# base_board5.net
KiCad netlist of a schematic drawn in EAGLE
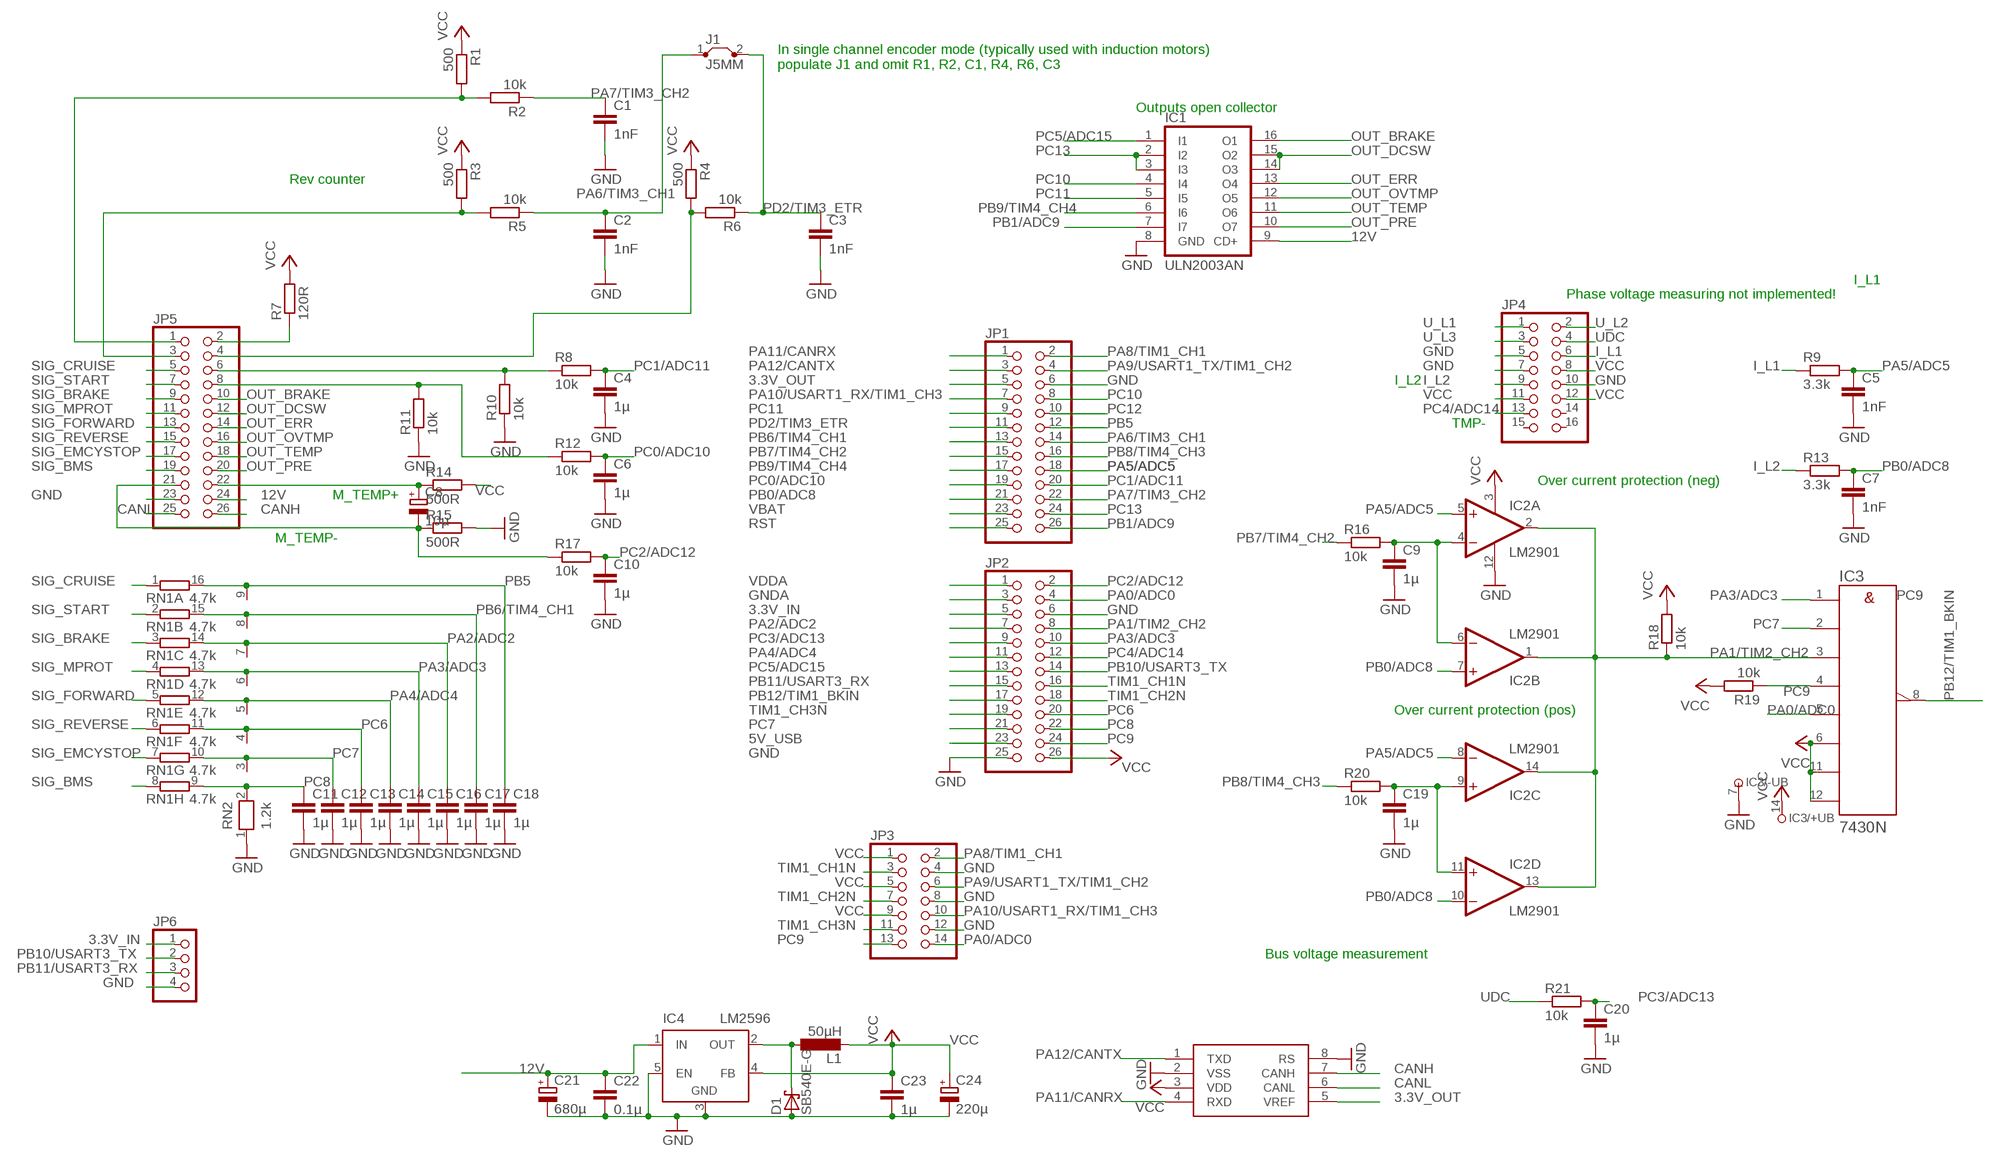
[diagram p0: schematic, sheet 1]

(export (version "E")
  (design (tool "Eeschema 10.0.6"))
  (components
    (comp (ref "C1")
      (value "1nF")
      (footprint "eagle-import:C025-024X044")
      (libsource (lib "eagle-import") (part "C-EU025-024X044"))
    )
    (comp (ref "C2")
      (value "1nF")
      (footprint "eagle-import:C025-024X044")
      (libsource (lib "eagle-import") (part "C-EU025-024X044"))
    )
    (comp (ref "C3")
      (value "1nF")
      (footprint "eagle-import:C025-024X044")
      (libsource (lib "eagle-import") (part "C-EU025-024X044"))
    )
    (comp (ref "C4")
      (value "1µ")
      (footprint "eagle-import:C025-024X044")
      (libsource (lib "eagle-import") (part "C-EU025-024X044"))
    )
    (comp (ref "C5")
      (value "1nF")
      (footprint "eagle-import:C025-024X044")
      (libsource (lib "eagle-import") (part "C-EU025-024X044"))
    )
    (comp (ref "C6")
      (value "1µ")
      (footprint "eagle-import:C025-024X044")
      (libsource (lib "eagle-import") (part "C-EU025-024X044"))
    )
    (comp (ref "C7")
      (value "1nF")
      (footprint "eagle-import:C025-024X044")
      (libsource (lib "eagle-import") (part "C-EU025-024X044"))
    )
    (comp (ref "C8")
      (value "10µ")
      (footprint "eagle-import:E2-4")
      (libsource (lib "eagle-import") (part "CPOL-EUE2-4"))
    )
    (comp (ref "C9")
      (value "1µ")
      (footprint "eagle-import:C025-024X044")
      (libsource (lib "eagle-import") (part "C-EU025-024X044"))
    )
    (comp (ref "C10")
      (value "1µ")
      (footprint "eagle-import:C025-024X044")
      (libsource (lib "eagle-import") (part "C-EU025-024X044"))
    )
    (comp (ref "C11")
      (value "1µ")
      (footprint "eagle-import:C025-024X044")
      (libsource (lib "eagle-import") (part "C-EU025-024X044"))
    )
    (comp (ref "C12")
      (value "1µ")
      (footprint "eagle-import:C025-024X044")
      (libsource (lib "eagle-import") (part "C-EU025-024X044"))
    )
    (comp (ref "C13")
      (value "1µ")
      (footprint "eagle-import:C025-024X044")
      (libsource (lib "eagle-import") (part "C-EU025-024X044"))
    )
    (comp (ref "C14")
      (value "1µ")
      (footprint "eagle-import:C025-024X044")
      (libsource (lib "eagle-import") (part "C-EU025-024X044"))
    )
    (comp (ref "C15")
      (value "1µ")
      (footprint "eagle-import:C025-024X044")
      (libsource (lib "eagle-import") (part "C-EU025-024X044"))
    )
    (comp (ref "C16")
      (value "1µ")
      (footprint "eagle-import:C025-024X044")
      (libsource (lib "eagle-import") (part "C-EU025-024X044"))
    )
    (comp (ref "C17")
      (value "1µ")
      (footprint "eagle-import:C025-024X044")
      (libsource (lib "eagle-import") (part "C-EU025-024X044"))
    )
    (comp (ref "C18")
      (value "1µ")
      (footprint "eagle-import:C025-024X044")
      (libsource (lib "eagle-import") (part "C-EU025-024X044"))
    )
    (comp (ref "C19")
      (value "1µ")
      (footprint "eagle-import:C025-024X044")
      (libsource (lib "eagle-import") (part "C-EU025-024X044"))
    )
    (comp (ref "C20")
      (value "1µ")
      (footprint "eagle-import:C025-024X044")
      (libsource (lib "eagle-import") (part "C-EU025-024X044"))
    )
    (comp (ref "C21")
      (value "680µ")
      (footprint "eagle-import:E2,5-5")
      (libsource (lib "eagle-import") (part "CPOL-EUE2.5-5"))
    )
    (comp (ref "C22")
      (value "0.1µ")
      (footprint "eagle-import:C050-024X044")
      (libsource (lib "eagle-import") (part "C-EU050-024X044"))
    )
    (comp (ref "C23")
      (value "1µ")
      (footprint "eagle-import:C025-024X044")
      (libsource (lib "eagle-import") (part "C-EU025-024X044"))
    )
    (comp (ref "C24")
      (value "220µ")
      (footprint "eagle-import:E2-4")
      (libsource (lib "eagle-import") (part "CPOL-EUE2-4"))
    )
    (comp (ref "D1")
      (value "SB540E-G")
      (footprint "eagle-import:DO201T15")
      (libsource (lib "eagle-import") (part "SCHOTTKY-DIODEDO201T15"))
    )
    (comp (ref "IC1")
      (value "ULN2003AN")
      (footprint "eagle-import:DIL16")
      (libsource (lib "eagle-import") (part "ULN2001AN"))
    )
    (comp (ref "IC2")
      (value "LM2901")
      (footprint "eagle-import:DIL14")
      (libsource (lib "eagle-import") (part "LM339N"))
    )
    (comp (ref "IC3")
      (value "7430N")
      (footprint "eagle-import:DIL14")
      (libsource (lib "eagle-import") (part "7430N"))
    )
    (comp (ref "IC4")
      (value "LM2596")
      (footprint "eagle-import:TO220-51")
      (libsource (lib "eagle-import") (part "LM2596TV"))
    )
    (comp (ref "IC5")
      (value "MCP2562P")
      (footprint "eagle-import:DIL08")
      (libsource (lib "eagle-import") (part "MCP2551P"))
    )
    (comp (ref "J1")
      (value "J5MM")
      (footprint "eagle-import:05")
      (libsource (lib "eagle-import") (part "J5MM"))
    )
    (comp (ref "JP1")
      (value "PINHD-2X13")
      (footprint "eagle-import:2X13")
      (libsource (lib "eagle-import") (part "PINHD-2X13"))
    )
    (comp (ref "JP2")
      (value "PINHD-2X13")
      (footprint "eagle-import:2X13")
      (libsource (lib "eagle-import") (part "PINHD-2X13"))
    )
    (comp (ref "JP3")
      (value "PINHD-2X7")
      (footprint "eagle-import:2X07")
      (libsource (lib "eagle-import") (part "PINHD-2X7"))
    )
    (comp (ref "JP4")
      (value "PINHD-2X8")
      (footprint "eagle-import:2X08")
      (libsource (lib "eagle-import") (part "PINHD-2X8"))
    )
    (comp (ref "JP5")
      (value "PINHD-2X13")
      (footprint "eagle-import:2X13")
      (libsource (lib "eagle-import") (part "PINHD-2X13"))
    )
    (comp (ref "JP6")
      (value "PINHD-1X4")
      (footprint "eagle-import:1X04")
      (libsource (lib "eagle-import") (part "PINHD-1X4"))
    )
    (comp (ref "L1")
      (value "50µH")
      (footprint "eagle-import:TJ3-U1")
      (libsource (lib "eagle-import") (part "L-EUTJ3-U1"))
    )
    (comp (ref "R1")
      (value "500")
      (footprint "eagle-import:0207_10")
      (libsource (lib "eagle-import") (part "R-EU_0207/10"))
    )
    (comp (ref "R2")
      (value "10k")
      (footprint "eagle-import:0207_10")
      (libsource (lib "eagle-import") (part "R-EU_0207/10"))
    )
    (comp (ref "R3")
      (value "500")
      (footprint "eagle-import:0207_10")
      (libsource (lib "eagle-import") (part "R-EU_0207/10"))
    )
    (comp (ref "R4")
      (value "500")
      (footprint "eagle-import:0207_10")
      (libsource (lib "eagle-import") (part "R-EU_0207/10"))
    )
    (comp (ref "R5")
      (value "10k")
      (footprint "eagle-import:0207_10")
      (libsource (lib "eagle-import") (part "R-EU_0207/10"))
    )
    (comp (ref "R6")
      (value "10k")
      (footprint "eagle-import:0207_10")
      (libsource (lib "eagle-import") (part "R-EU_0207/10"))
    )
    (comp (ref "R7")
      (value "120R")
      (footprint "eagle-import:0207_10")
      (libsource (lib "eagle-import") (part "R-EU_0207/10"))
    )
    (comp (ref "R8")
      (value "10k")
      (footprint "eagle-import:0207_10")
      (libsource (lib "eagle-import") (part "R-EU_0207/10"))
    )
    (comp (ref "R9")
      (value "3.3k")
      (footprint "eagle-import:0207_10")
      (libsource (lib "eagle-import") (part "R-EU_0207/10"))
    )
    (comp (ref "R10")
      (value "10k")
      (footprint "eagle-import:0207_10")
      (libsource (lib "eagle-import") (part "R-EU_0207/10"))
    )
    (comp (ref "R11")
      (value "10k")
      (footprint "eagle-import:0207_10")
      (libsource (lib "eagle-import") (part "R-EU_0207/10"))
    )
    (comp (ref "R12")
      (value "10k")
      (footprint "eagle-import:0207_10")
      (libsource (lib "eagle-import") (part "R-EU_0207/10"))
    )
    (comp (ref "R13")
      (value "3.3k")
      (footprint "eagle-import:0207_10")
      (libsource (lib "eagle-import") (part "R-EU_0207/10"))
    )
    (comp (ref "R14")
      (value "500R")
      (footprint "eagle-import:0207_10")
      (libsource (lib "eagle-import") (part "R-EU_0207/10"))
    )
    (comp (ref "R15")
      (value "500R")
      (footprint "eagle-import:0207_10")
      (libsource (lib "eagle-import") (part "R-EU_0207/10"))
    )
    (comp (ref "R16")
      (value "10k")
      (footprint "eagle-import:0207_10")
      (libsource (lib "eagle-import") (part "R-EU_0207/10"))
    )
    (comp (ref "R17")
      (value "10k")
      (footprint "eagle-import:0207_10")
      (libsource (lib "eagle-import") (part "R-EU_0207/10"))
    )
    (comp (ref "R18")
      (value "10k")
      (footprint "eagle-import:0207_10")
      (libsource (lib "eagle-import") (part "R-EU_0207/10"))
    )
    (comp (ref "R19")
      (value "10k")
      (footprint "eagle-import:0207_10")
      (libsource (lib "eagle-import") (part "R-EU_0207/10"))
    )
    (comp (ref "R20")
      (value "10k")
      (footprint "eagle-import:0207_10")
      (libsource (lib "eagle-import") (part "R-EU_0207/10"))
    )
    (comp (ref "R21")
      (value "10k")
      (footprint "eagle-import:0207_10")
      (libsource (lib "eagle-import") (part "R-EU_0207/10"))
    )
    (comp (ref "RN1")
      (value "4.7k")
      (footprint "eagle-import:DIL16")
      (libsource (lib "eagle-import") (part "8R-N"))
    )
    (comp (ref "RN2")
      (value "1.2k")
      (footprint "eagle-import:RN-9")
      (libsource (lib "eagle-import") (part "RN08"))
    )
  )
  (nets
    (net (code "1") (name "/3.3V_IN") (class "Default")
      (node (ref "JP2") (pin "5") (pinfunction "5_5") (pintype "passive"))
      (node (ref "JP6") (pin "1") (pinfunction "1_1") (pintype "passive"))
    )
    (net (code "2") (name "/3.3V_OUT") (class "Default")
      (node (ref "IC5") (pin "5") (pinfunction "VREF_5") (pintype "bidirectional"))
      (node (ref "JP1") (pin "5") (pinfunction "5_5") (pintype "passive"))
    )
    (net (code "3") (name "/5V_USB") (class "Default")
      (node (ref "JP2") (pin "23") (pinfunction "23_23") (pintype "passive"))
    )
    (net (code "4") (name "/12V") (class "Default")
      (node (ref "C21") (pin "+") (pinfunction "+_+") (pintype "passive"))
      (node (ref "C22") (pin "1") (pinfunction "1_1") (pintype "passive"))
      (node (ref "IC1") (pin "9") (pinfunction "CD+_9") (pintype "passive"))
      (node (ref "IC4") (pin "1") (pinfunction "IN_1") (pintype "input"))
      (node (ref "JP5") (pin "24") (pinfunction "24_24") (pintype "passive"))
    )
    (net (code "5") (name "/CANH") (class "Default")
      (node (ref "IC5") (pin "7") (pinfunction "CANH_7") (pintype "bidirectional"))
      (node (ref "JP5") (pin "26") (pinfunction "26_26") (pintype "passive"))
    )
    (net (code "6") (name "/CANL") (class "Default")
      (node (ref "IC5") (pin "6") (pinfunction "CANL_6") (pintype "bidirectional"))
      (node (ref "JP5") (pin "25") (pinfunction "25_25") (pintype "passive"))
    )
    (net (code "7") (name "/GNDA") (class "Default")
      (node (ref "JP2") (pin "3") (pinfunction "3_3") (pintype "passive"))
    )
    (net (code "8") (name "/I_L1") (class "Default")
      (node (ref "JP4") (pin "6") (pinfunction "6_6") (pintype "passive"))
      (node (ref "R9") (pin "1") (pinfunction "1_1") (pintype "passive"))
    )
    (net (code "9") (name "/I_L2") (class "Default")
      (node (ref "JP4") (pin "9") (pinfunction "9_9") (pintype "passive"))
      (node (ref "R13") (pin "1") (pinfunction "1_1") (pintype "passive"))
    )
    (net (code "10") (name "/OUT_BRAKE") (class "Default")
      (node (ref "IC1") (pin "16") (pinfunction "O1_16") (pintype "open_collector"))
      (node (ref "JP5") (pin "10") (pinfunction "10_10") (pintype "passive"))
    )
    (net (code "11") (name "/OUT_DCSW") (class "Default")
      (node (ref "IC1") (pin "14") (pinfunction "O3_14") (pintype "open_collector"))
      (node (ref "IC1") (pin "15") (pinfunction "O2_15") (pintype "open_collector"))
      (node (ref "JP5") (pin "12") (pinfunction "12_12") (pintype "passive"))
    )
    (net (code "12") (name "/OUT_ERR") (class "Default")
      (node (ref "IC1") (pin "13") (pinfunction "O4_13") (pintype "open_collector"))
      (node (ref "JP5") (pin "14") (pinfunction "14_14") (pintype "passive"))
    )
    (net (code "13") (name "/OUT_OVTMP") (class "Default")
      (node (ref "IC1") (pin "12") (pinfunction "O5_12") (pintype "open_collector"))
      (node (ref "JP5") (pin "16") (pinfunction "16_16") (pintype "passive"))
    )
    (net (code "14") (name "/OUT_PRE") (class "Default")
      (node (ref "IC1") (pin "10") (pinfunction "O7_10") (pintype "open_collector"))
      (node (ref "JP5") (pin "20") (pinfunction "20_20") (pintype "passive"))
    )
    (net (code "15") (name "/OUT_TEMP") (class "Default")
      (node (ref "IC1") (pin "11") (pinfunction "O6_11") (pintype "open_collector"))
      (node (ref "JP5") (pin "18") (pinfunction "18_18") (pintype "passive"))
    )
    (net (code "16") (name "/PA0{slash}ADC0") (class "Default")
      (node (ref "IC3") (pin "5") (pinfunction "E_5") (pintype "input"))
      (node (ref "JP2") (pin "4") (pinfunction "4_4") (pintype "passive"))
      (node (ref "JP3") (pin "14") (pinfunction "14_14") (pintype "passive"))
    )
    (net (code "17") (name "/PA1{slash}TIM2_CH2") (class "Default")
      (node (ref "IC2") (pin "1") (pinfunction "OUT_1") (pintype "open_collector"))
      (node (ref "IC2") (pin "13") (pinfunction "OUT_13") (pintype "open_collector"))
      (node (ref "IC2") (pin "14") (pinfunction "OUT_14") (pintype "open_collector"))
      (node (ref "IC2") (pin "2") (pinfunction "OUT_2") (pintype "open_collector"))
      (node (ref "IC3") (pin "3") (pinfunction "C_3") (pintype "input"))
      (node (ref "JP2") (pin "8") (pinfunction "8_8") (pintype "passive"))
      (node (ref "R18") (pin "1") (pinfunction "1_1") (pintype "passive"))
    )
    (net (code "18") (name "/PA2{slash}ADC2") (class "Default")
      (node (ref "C16") (pin "1") (pinfunction "1_1") (pintype "passive"))
      (node (ref "JP2") (pin "7") (pinfunction "7_7") (pintype "passive"))
      (node (ref "RN1") (pin "14") (pinfunction "2_14") (pintype "passive"))
      (node (ref "RN2") (pin "7") (pinfunction "7_7") (pintype "passive"))
    )
    (net (code "19") (name "/PA3{slash}ADC3") (class "Default")
      (node (ref "C15") (pin "1") (pinfunction "1_1") (pintype "passive"))
      (node (ref "IC3") (pin "1") (pinfunction "A_1") (pintype "input"))
      (node (ref "JP2") (pin "10") (pinfunction "10_10") (pintype "passive"))
      (node (ref "RN1") (pin "13") (pinfunction "2_13") (pintype "passive"))
      (node (ref "RN2") (pin "6") (pinfunction "6_6") (pintype "passive"))
    )
    (net (code "20") (name "/PA4{slash}ADC4") (class "Default")
      (node (ref "C14") (pin "1") (pinfunction "1_1") (pintype "passive"))
      (node (ref "JP2") (pin "11") (pinfunction "11_11") (pintype "passive"))
      (node (ref "RN1") (pin "12") (pinfunction "2_12") (pintype "passive"))
      (node (ref "RN2") (pin "5") (pinfunction "5_5") (pintype "passive"))
    )
    (net (code "21") (name "/PA5{slash}ADC5") (class "Default")
      (node (ref "C5") (pin "1") (pinfunction "1_1") (pintype "passive"))
      (node (ref "IC2") (pin "5") (pinfunction "+IN_5") (pintype "input"))
      (node (ref "IC2") (pin "8") (pinfunction "-IN_8") (pintype "input"))
      (node (ref "JP1") (pin "18") (pinfunction "18_18") (pintype "passive"))
      (node (ref "R9") (pin "2") (pinfunction "2_2") (pintype "passive"))
    )
    (net (code "22") (name "/PA6{slash}TIM3_CH1") (class "Default")
      (node (ref "C2") (pin "1") (pinfunction "1_1") (pintype "passive"))
      (node (ref "J1") (pin "1") (pinfunction "1_1") (pintype "passive"))
      (node (ref "JP1") (pin "14") (pinfunction "14_14") (pintype "passive"))
      (node (ref "R5") (pin "1") (pinfunction "1_1") (pintype "passive"))
    )
    (net (code "23") (name "/PA7{slash}TIM3_CH2") (class "Default")
      (node (ref "C1") (pin "1") (pinfunction "1_1") (pintype "passive"))
      (node (ref "JP1") (pin "22") (pinfunction "22_22") (pintype "passive"))
      (node (ref "R2") (pin "1") (pinfunction "1_1") (pintype "passive"))
    )
    (net (code "24") (name "/PA8{slash}TIM1_CH1") (class "Default")
      (node (ref "JP1") (pin "2") (pinfunction "2_2") (pintype "passive"))
      (node (ref "JP3") (pin "2") (pinfunction "2_2") (pintype "passive"))
    )
    (net (code "25") (name "/PA9{slash}USART1_TX{slash}TIM1_CH2") (class "Default")
      (node (ref "JP1") (pin "4") (pinfunction "4_4") (pintype "passive"))
      (node (ref "JP3") (pin "6") (pinfunction "6_6") (pintype "passive"))
    )
    (net (code "26") (name "/PA10{slash}USART1_RX{slash}TIM1_CH3") (class "Default")
      (node (ref "JP1") (pin "7") (pinfunction "7_7") (pintype "passive"))
      (node (ref "JP3") (pin "10") (pinfunction "10_10") (pintype "passive"))
    )
    (net (code "27") (name "/PA11{slash}CANRX") (class "Default")
      (node (ref "IC5") (pin "4") (pinfunction "RXD_4") (pintype "bidirectional"))
      (node (ref "JP1") (pin "1") (pinfunction "1_1") (pintype "passive"))
    )
    (net (code "28") (name "/PA12{slash}CANTX") (class "Default")
      (node (ref "IC5") (pin "1") (pinfunction "TXD_1") (pintype "bidirectional"))
      (node (ref "JP1") (pin "3") (pinfunction "3_3") (pintype "passive"))
    )
    (net (code "29") (name "/PB0{slash}ADC8") (class "Default")
      (node (ref "C7") (pin "1") (pinfunction "1_1") (pintype "passive"))
      (node (ref "IC2") (pin "10") (pinfunction "-IN_10") (pintype "input"))
      (node (ref "IC2") (pin "7") (pinfunction "+IN_7") (pintype "input"))
      (node (ref "JP1") (pin "21") (pinfunction "21_21") (pintype "passive"))
      (node (ref "R13") (pin "2") (pinfunction "2_2") (pintype "passive"))
    )
    (net (code "30") (name "/PB1{slash}ADC9") (class "Default")
      (node (ref "IC1") (pin "7") (pinfunction "I7_7") (pintype "input"))
      (node (ref "JP1") (pin "26") (pinfunction "26_26") (pintype "passive"))
    )
    (net (code "31") (name "/PB5") (class "Default")
      (node (ref "C18") (pin "1") (pinfunction "1_1") (pintype "passive"))
      (node (ref "JP1") (pin "12") (pinfunction "12_12") (pintype "passive"))
      (node (ref "RN1") (pin "16") (pinfunction "2_16") (pintype "passive"))
      (node (ref "RN2") (pin "9") (pinfunction "9_9") (pintype "passive"))
    )
    (net (code "32") (name "/PB6{slash}TIM4_CH1") (class "Default")
      (node (ref "C17") (pin "1") (pinfunction "1_1") (pintype "passive"))
      (node (ref "JP1") (pin "13") (pinfunction "13_13") (pintype "passive"))
      (node (ref "RN1") (pin "15") (pinfunction "2_15") (pintype "passive"))
      (node (ref "RN2") (pin "8") (pinfunction "8_8") (pintype "passive"))
    )
    (net (code "33") (name "/PB7{slash}TIM4_CH2") (class "Default")
      (node (ref "JP1") (pin "15") (pinfunction "15_15") (pintype "passive"))
      (node (ref "R16") (pin "1") (pinfunction "1_1") (pintype "passive"))
    )
    (net (code "34") (name "/PB8{slash}TIM4_CH3") (class "Default")
      (node (ref "JP1") (pin "16") (pinfunction "16_16") (pintype "passive"))
      (node (ref "R20") (pin "1") (pinfunction "1_1") (pintype "passive"))
    )
    (net (code "35") (name "/PB9{slash}TIM4_CH4") (class "Default")
      (node (ref "IC1") (pin "6") (pinfunction "I6_6") (pintype "input"))
      (node (ref "JP1") (pin "17") (pinfunction "17_17") (pintype "passive"))
    )
    (net (code "36") (name "/PB10{slash}USART3_TX") (class "Default")
      (node (ref "JP2") (pin "14") (pinfunction "14_14") (pintype "passive"))
      (node (ref "JP6") (pin "2") (pinfunction "2_2") (pintype "passive"))
    )
    (net (code "37") (name "/PB11{slash}USART3_RX") (class "Default")
      (node (ref "JP2") (pin "15") (pinfunction "15_15") (pintype "passive"))
      (node (ref "JP6") (pin "3") (pinfunction "3_3") (pintype "passive"))
    )
    (net (code "38") (name "/PB12{slash}TIM1_BKIN") (class "Default")
      (node (ref "IC3") (pin "8") (pinfunction "Y_8") (pintype "output"))
      (node (ref "JP2") (pin "17") (pinfunction "17_17") (pintype "passive"))
    )
    (net (code "39") (name "/PC0{slash}ADC10") (class "Default")
      (node (ref "C6") (pin "1") (pinfunction "1_1") (pintype "passive"))
      (node (ref "JP1") (pin "19") (pinfunction "19_19") (pintype "passive"))
      (node (ref "R12") (pin "2") (pinfunction "2_2") (pintype "passive"))
    )
    (net (code "40") (name "/PC1{slash}ADC11") (class "Default")
      (node (ref "C4") (pin "1") (pinfunction "1_1") (pintype "passive"))
      (node (ref "JP1") (pin "20") (pinfunction "20_20") (pintype "passive"))
      (node (ref "R8") (pin "2") (pinfunction "2_2") (pintype "passive"))
    )
    (net (code "41") (name "/PC2{slash}ADC12") (class "Default")
      (node (ref "C10") (pin "1") (pinfunction "1_1") (pintype "passive"))
      (node (ref "JP2") (pin "2") (pinfunction "2_2") (pintype "passive"))
      (node (ref "R17") (pin "2") (pinfunction "2_2") (pintype "passive"))
    )
    (net (code "42") (name "/PC3{slash}ADC13") (class "Default")
      (node (ref "C20") (pin "1") (pinfunction "1_1") (pintype "passive"))
      (node (ref "JP2") (pin "9") (pinfunction "9_9") (pintype "passive"))
      (node (ref "R21") (pin "2") (pinfunction "2_2") (pintype "passive"))
    )
    (net (code "43") (name "/PC4{slash}ADC14") (class "Default")
      (node (ref "JP2") (pin "12") (pinfunction "12_12") (pintype "passive"))
      (node (ref "JP4") (pin "13") (pinfunction "13_13") (pintype "passive"))
    )
    (net (code "44") (name "/PC5{slash}ADC15") (class "Default")
      (node (ref "IC1") (pin "1") (pinfunction "I1_1") (pintype "input"))
      (node (ref "JP2") (pin "13") (pinfunction "13_13") (pintype "passive"))
    )
    (net (code "45") (name "/PC6") (class "Default")
      (node (ref "C13") (pin "1") (pinfunction "1_1") (pintype "passive"))
      (node (ref "JP2") (pin "20") (pinfunction "20_20") (pintype "passive"))
      (node (ref "RN1") (pin "11") (pinfunction "2_11") (pintype "passive"))
      (node (ref "RN2") (pin "4") (pinfunction "4_4") (pintype "passive"))
    )
    (net (code "46") (name "/PC7") (class "Default")
      (node (ref "C12") (pin "1") (pinfunction "1_1") (pintype "passive"))
      (node (ref "IC3") (pin "2") (pinfunction "B_2") (pintype "input"))
      (node (ref "JP2") (pin "21") (pinfunction "21_21") (pintype "passive"))
      (node (ref "RN1") (pin "10") (pinfunction "2_10") (pintype "passive"))
      (node (ref "RN2") (pin "3") (pinfunction "3_3") (pintype "passive"))
    )
    (net (code "47") (name "/PC8") (class "Default")
      (node (ref "C11") (pin "1") (pinfunction "1_1") (pintype "passive"))
      (node (ref "JP2") (pin "22") (pinfunction "22_22") (pintype "passive"))
      (node (ref "RN1") (pin "9") (pinfunction "2_9") (pintype "passive"))
      (node (ref "RN2") (pin "2") (pinfunction "2_2") (pintype "passive"))
    )
    (net (code "48") (name "/PC9") (class "Default")
      (node (ref "IC3") (pin "4") (pinfunction "D_4") (pintype "input"))
      (node (ref "JP2") (pin "24") (pinfunction "24_24") (pintype "passive"))
      (node (ref "JP3") (pin "13") (pinfunction "13_13") (pintype "passive"))
      (node (ref "R19") (pin "1") (pinfunction "1_1") (pintype "passive"))
    )
    (net (code "49") (name "/PC10") (class "Default")
      (node (ref "IC1") (pin "4") (pinfunction "I4_4") (pintype "input"))
      (node (ref "JP1") (pin "8") (pinfunction "8_8") (pintype "passive"))
    )
    (net (code "50") (name "/PC11") (class "Default")
      (node (ref "IC1") (pin "5") (pinfunction "I5_5") (pintype "input"))
      (node (ref "JP1") (pin "9") (pinfunction "9_9") (pintype "passive"))
    )
    (net (code "51") (name "/PC12") (class "Default")
      (node (ref "JP1") (pin "10") (pinfunction "10_10") (pintype "passive"))
    )
    (net (code "52") (name "/PC13") (class "Default")
      (node (ref "IC1") (pin "2") (pinfunction "I2_2") (pintype "input"))
      (node (ref "IC1") (pin "3") (pinfunction "I3_3") (pintype "input"))
      (node (ref "JP1") (pin "24") (pinfunction "24_24") (pintype "passive"))
    )
    (net (code "53") (name "/PD2{slash}TIM3_ETR") (class "Default")
      (node (ref "C3") (pin "1") (pinfunction "1_1") (pintype "passive"))
      (node (ref "J1") (pin "2") (pinfunction "2_2") (pintype "passive"))
      (node (ref "JP1") (pin "11") (pinfunction "11_11") (pintype "passive"))
      (node (ref "R6") (pin "1") (pinfunction "1_1") (pintype "passive"))
    )
    (net (code "54") (name "/RST") (class "Default")
      (node (ref "JP1") (pin "25") (pinfunction "25_25") (pintype "passive"))
    )
    (net (code "55") (name "/SIG_BMS") (class "Default")
      (node (ref "JP5") (pin "19") (pinfunction "19_19") (pintype "passive"))
      (node (ref "RN1") (pin "8") (pinfunction "1_8") (pintype "passive"))
    )
    (net (code "56") (name "/SIG_BRAKE") (class "Default")
      (node (ref "JP5") (pin "9") (pinfunction "9_9") (pintype "passive"))
      (node (ref "RN1") (pin "3") (pinfunction "1_3") (pintype "passive"))
    )
    (net (code "57") (name "/SIG_CRUISE") (class "Default")
      (node (ref "JP5") (pin "5") (pinfunction "5_5") (pintype "passive"))
      (node (ref "RN1") (pin "1") (pinfunction "1_1") (pintype "passive"))
    )
    (net (code "58") (name "/SIG_EMCYSTOP") (class "Default")
      (node (ref "JP5") (pin "17") (pinfunction "17_17") (pintype "passive"))
      (node (ref "RN1") (pin "7") (pinfunction "1_7") (pintype "passive"))
    )
    (net (code "59") (name "/SIG_FORWARD") (class "Default")
      (node (ref "JP5") (pin "13") (pinfunction "13_13") (pintype "passive"))
      (node (ref "RN1") (pin "5") (pinfunction "1_5") (pintype "passive"))
    )
    (net (code "60") (name "/SIG_MPROT") (class "Default")
      (node (ref "JP5") (pin "11") (pinfunction "11_11") (pintype "passive"))
      (node (ref "RN1") (pin "4") (pinfunction "1_4") (pintype "passive"))
    )
    (net (code "61") (name "/SIG_REVERSE") (class "Default")
      (node (ref "JP5") (pin "15") (pinfunction "15_15") (pintype "passive"))
      (node (ref "RN1") (pin "6") (pinfunction "1_6") (pintype "passive"))
    )
    (net (code "62") (name "/SIG_START") (class "Default")
      (node (ref "JP5") (pin "7") (pinfunction "7_7") (pintype "passive"))
      (node (ref "RN1") (pin "2") (pinfunction "1_2") (pintype "passive"))
    )
    (net (code "63") (name "/TIM1_CH1N") (class "Default")
      (node (ref "JP2") (pin "16") (pinfunction "16_16") (pintype "passive"))
      (node (ref "JP3") (pin "3") (pinfunction "3_3") (pintype "passive"))
    )
    (net (code "64") (name "/TIM1_CH2N") (class "Default")
      (node (ref "JP2") (pin "18") (pinfunction "18_18") (pintype "passive"))
      (node (ref "JP3") (pin "7") (pinfunction "7_7") (pintype "passive"))
    )
    (net (code "65") (name "/TIM1_CH3N") (class "Default")
      (node (ref "JP2") (pin "19") (pinfunction "19_19") (pintype "passive"))
      (node (ref "JP3") (pin "11") (pinfunction "11_11") (pintype "passive"))
    )
    (net (code "66") (name "/UDC") (class "Default")
      (node (ref "JP4") (pin "4") (pinfunction "4_4") (pintype "passive"))
      (node (ref "R21") (pin "1") (pinfunction "1_1") (pintype "passive"))
    )
    (net (code "67") (name "/U_L1") (class "Default")
      (node (ref "JP4") (pin "1") (pinfunction "1_1") (pintype "passive"))
    )
    (net (code "68") (name "/U_L2") (class "Default")
      (node (ref "JP4") (pin "2") (pinfunction "2_2") (pintype "passive"))
    )
    (net (code "69") (name "/U_L3") (class "Default")
      (node (ref "JP4") (pin "3") (pinfunction "3_3") (pintype "passive"))
    )
    (net (code "70") (name "/VBAT") (class "Default")
      (node (ref "JP1") (pin "23") (pinfunction "23_23") (pintype "passive"))
    )
    (net (code "71") (name "/VDDA") (class "Default")
      (node (ref "JP2") (pin "1") (pinfunction "1_1") (pintype "passive"))
    )
    (net (code "72") (name "GND") (class "Default")
      (node (ref "C1") (pin "2") (pinfunction "2_2") (pintype "passive"))
      (node (ref "C10") (pin "2") (pinfunction "2_2") (pintype "passive"))
      (node (ref "C11") (pin "2") (pinfunction "2_2") (pintype "passive"))
      (node (ref "C12") (pin "2") (pinfunction "2_2") (pintype "passive"))
      (node (ref "C13") (pin "2") (pinfunction "2_2") (pintype "passive"))
      (node (ref "C14") (pin "2") (pinfunction "2_2") (pintype "passive"))
      (node (ref "C15") (pin "2") (pinfunction "2_2") (pintype "passive"))
      (node (ref "C16") (pin "2") (pinfunction "2_2") (pintype "passive"))
      (node (ref "C17") (pin "2") (pinfunction "2_2") (pintype "passive"))
      (node (ref "C18") (pin "2") (pinfunction "2_2") (pintype "passive"))
      (node (ref "C19") (pin "2") (pinfunction "2_2") (pintype "passive"))
      (node (ref "C2") (pin "2") (pinfunction "2_2") (pintype "passive"))
      (node (ref "C20") (pin "2") (pinfunction "2_2") (pintype "passive"))
      (node (ref "C21") (pin "-") (pinfunction "-_-") (pintype "passive"))
      (node (ref "C22") (pin "2") (pinfunction "2_2") (pintype "passive"))
      (node (ref "C23") (pin "2") (pinfunction "2_2") (pintype "passive"))
      (node (ref "C24") (pin "-") (pinfunction "-_-") (pintype "passive"))
      (node (ref "C3") (pin "2") (pinfunction "2_2") (pintype "passive"))
      (node (ref "C4") (pin "2") (pinfunction "2_2") (pintype "passive"))
      (node (ref "C5") (pin "2") (pinfunction "2_2") (pintype "passive"))
      (node (ref "C6") (pin "2") (pinfunction "2_2") (pintype "passive"))
      (node (ref "C7") (pin "2") (pinfunction "2_2") (pintype "passive"))
      (node (ref "C9") (pin "2") (pinfunction "2_2") (pintype "passive"))
      (node (ref "D1") (pin "A") (pinfunction "A_A") (pintype "passive"))
      (node (ref "IC1") (pin "8") (pinfunction "GND_8") (pintype "power_in"))
      (node (ref "IC2") (pin "12") (pinfunction "GND_12") (pintype "power_in"))
      (node (ref "IC3") (pin "7") (pinfunction "-UB_7") (pintype "power_in"))
      (node (ref "IC4") (pin "3") (pinfunction "GND_3") (pintype "power_in"))
      (node (ref "IC4") (pin "5") (pinfunction "EN_5") (pintype "input"))
      (node (ref "IC5") (pin "2") (pinfunction "VSS_2") (pintype "bidirectional"))
      (node (ref "IC5") (pin "8") (pinfunction "RS_8") (pintype "bidirectional"))
      (node (ref "JP1") (pin "6") (pinfunction "6_6") (pintype "passive"))
      (node (ref "JP2") (pin "25") (pinfunction "25_25") (pintype "passive"))
      (node (ref "JP2") (pin "6") (pinfunction "6_6") (pintype "passive"))
      (node (ref "JP3") (pin "12") (pinfunction "12_12") (pintype "passive"))
      (node (ref "JP3") (pin "4") (pinfunction "4_4") (pintype "passive"))
      (node (ref "JP3") (pin "8") (pinfunction "8_8") (pintype "passive"))
      (node (ref "JP4") (pin "10") (pinfunction "10_10") (pintype "passive"))
      (node (ref "JP4") (pin "5") (pinfunction "5_5") (pintype "passive"))
      (node (ref "JP4") (pin "7") (pinfunction "7_7") (pintype "passive"))
      (node (ref "JP5") (pin "23") (pinfunction "23_23") (pintype "passive"))
      (node (ref "JP6") (pin "4") (pinfunction "4_4") (pintype "passive"))
      (node (ref "R10") (pin "1") (pinfunction "1_1") (pintype "passive"))
      (node (ref "R11") (pin "1") (pinfunction "1_1") (pintype "passive"))
      (node (ref "R15") (pin "2") (pinfunction "2_2") (pintype "passive"))
      (node (ref "RN2") (pin "1") (pinfunction "1_1") (pintype "passive"))
    )
    (net (code "73") (name "Net-(C8-Pad+)") (class "Default")
      (node (ref "C8") (pin "+") (pinfunction "+_+") (pintype "passive"))
      (node (ref "JP5") (pin "22") (pinfunction "22_22") (pintype "passive"))
      (node (ref "R14") (pin "1") (pinfunction "1_1") (pintype "passive"))
    )
    (net (code "74") (name "Net-(C8-Pad-)") (class "Default")
      (node (ref "C8") (pin "-") (pinfunction "-_-") (pintype "passive"))
      (node (ref "JP5") (pin "21") (pinfunction "21_21") (pintype "passive"))
      (node (ref "R15") (pin "1") (pinfunction "1_1") (pintype "passive"))
      (node (ref "R17") (pin "1") (pinfunction "1_1") (pintype "passive"))
    )
    (net (code "75") (name "Net-(IC2A--IN)") (class "Default")
      (node (ref "C9") (pin "1") (pinfunction "1_1") (pintype "passive"))
      (node (ref "IC2") (pin "4") (pinfunction "-IN_4") (pintype "input"))
      (node (ref "IC2") (pin "6") (pinfunction "-IN_6") (pintype "input"))
      (node (ref "R16") (pin "2") (pinfunction "2_2") (pintype "passive"))
    )
    (net (code "76") (name "Net-(IC2C-+IN)") (class "Default")
      (node (ref "C19") (pin "1") (pinfunction "1_1") (pintype "passive"))
      (node (ref "IC2") (pin "11") (pinfunction "+IN_11") (pintype "input"))
      (node (ref "IC2") (pin "9") (pinfunction "+IN_9") (pintype "input"))
      (node (ref "R20") (pin "2") (pinfunction "2_2") (pintype "passive"))
    )
    (net (code "77") (name "Net-(IC4-OUT)") (class "Default")
      (node (ref "D1") (pin "C") (pinfunction "C_C") (pintype "passive"))
      (node (ref "IC4") (pin "2") (pinfunction "OUT_2") (pintype "output"))
      (node (ref "L1") (pin "1") (pinfunction "1_1") (pintype "passive"))
    )
    (net (code "78") (name "Net-(JP5-Pad1)") (class "Default")
      (node (ref "JP5") (pin "1") (pinfunction "1_1") (pintype "passive"))
      (node (ref "R1") (pin "2") (pinfunction "2_2") (pintype "passive"))
      (node (ref "R2") (pin "2") (pinfunction "2_2") (pintype "passive"))
    )
    (net (code "79") (name "Net-(JP5-Pad2)") (class "Default")
      (node (ref "JP5") (pin "2") (pinfunction "2_2") (pintype "passive"))
      (node (ref "R7") (pin "1") (pinfunction "1_1") (pintype "passive"))
    )
    (net (code "80") (name "Net-(JP5-Pad3)") (class "Default")
      (node (ref "JP5") (pin "3") (pinfunction "3_3") (pintype "passive"))
      (node (ref "R3") (pin "2") (pinfunction "2_2") (pintype "passive"))
      (node (ref "R5") (pin "2") (pinfunction "2_2") (pintype "passive"))
    )
    (net (code "81") (name "Net-(JP5-Pad4)") (class "Default")
      (node (ref "JP5") (pin "4") (pinfunction "4_4") (pintype "passive"))
      (node (ref "R4") (pin "2") (pinfunction "2_2") (pintype "passive"))
      (node (ref "R6") (pin "2") (pinfunction "2_2") (pintype "passive"))
    )
    (net (code "82") (name "Net-(JP5-Pad6)") (class "Default")
      (node (ref "JP5") (pin "6") (pinfunction "6_6") (pintype "passive"))
      (node (ref "R10") (pin "2") (pinfunction "2_2") (pintype "passive"))
      (node (ref "R8") (pin "1") (pinfunction "1_1") (pintype "passive"))
    )
    (net (code "83") (name "Net-(JP5-Pad8)") (class "Default")
      (node (ref "JP5") (pin "8") (pinfunction "8_8") (pintype "passive"))
      (node (ref "R11") (pin "2") (pinfunction "2_2") (pintype "passive"))
      (node (ref "R12") (pin "1") (pinfunction "1_1") (pintype "passive"))
    )
    (net (code "84") (name "VCC") (class "Default")
      (node (ref "C23") (pin "1") (pinfunction "1_1") (pintype "passive"))
      (node (ref "C24") (pin "+") (pinfunction "+_+") (pintype "passive"))
      (node (ref "IC2") (pin "3") (pinfunction "V+_3") (pintype "power_in"))
      (node (ref "IC3") (pin "11") (pinfunction "G_11") (pintype "input"))
      (node (ref "IC3") (pin "12") (pinfunction "H_12") (pintype "input"))
      (node (ref "IC3") (pin "14") (pinfunction "+UB_14") (pintype "power_in"))
      (node (ref "IC3") (pin "6") (pinfunction "F_6") (pintype "input"))
      (node (ref "IC4") (pin "4") (pinfunction "FB_4") (pintype "input"))
      (node (ref "IC5") (pin "3") (pinfunction "VDD_3") (pintype "bidirectional"))
      (node (ref "JP2") (pin "26") (pinfunction "26_26") (pintype "passive"))
      (node (ref "JP3") (pin "1") (pinfunction "1_1") (pintype "passive"))
      (node (ref "JP3") (pin "5") (pinfunction "5_5") (pintype "passive"))
      (node (ref "JP3") (pin "9") (pinfunction "9_9") (pintype "passive"))
      (node (ref "JP4") (pin "11") (pinfunction "11_11") (pintype "passive"))
      (node (ref "JP4") (pin "12") (pinfunction "12_12") (pintype "passive"))
      (node (ref "JP4") (pin "8") (pinfunction "8_8") (pintype "passive"))
      (node (ref "L1") (pin "2") (pinfunction "2_2") (pintype "passive"))
      (node (ref "R1") (pin "1") (pinfunction "1_1") (pintype "passive"))
      (node (ref "R14") (pin "2") (pinfunction "2_2") (pintype "passive"))
      (node (ref "R18") (pin "2") (pinfunction "2_2") (pintype "passive"))
      (node (ref "R19") (pin "2") (pinfunction "2_2") (pintype "passive"))
      (node (ref "R3") (pin "1") (pinfunction "1_1") (pintype "passive"))
      (node (ref "R4") (pin "1") (pinfunction "1_1") (pintype "passive"))
      (node (ref "R7") (pin "2") (pinfunction "2_2") (pintype "passive"))
    )
    (net (code "85") (name "unconnected-(JP4-Pad14)") (class "Default")
      (node (ref "JP4") (pin "14") (pinfunction "14_14") (pintype "passive"))
    )
    (net (code "86") (name "unconnected-(JP4-Pad15)") (class "Default")
      (node (ref "JP4") (pin "15") (pinfunction "15_15") (pintype "passive"))
    )
    (net (code "87") (name "unconnected-(JP4-Pad16)") (class "Default")
      (node (ref "JP4") (pin "16") (pinfunction "16_16") (pintype "passive"))
    )
  )
)
